# duaghter.net
KiCad netlist of a schematic drawn in EAGLE
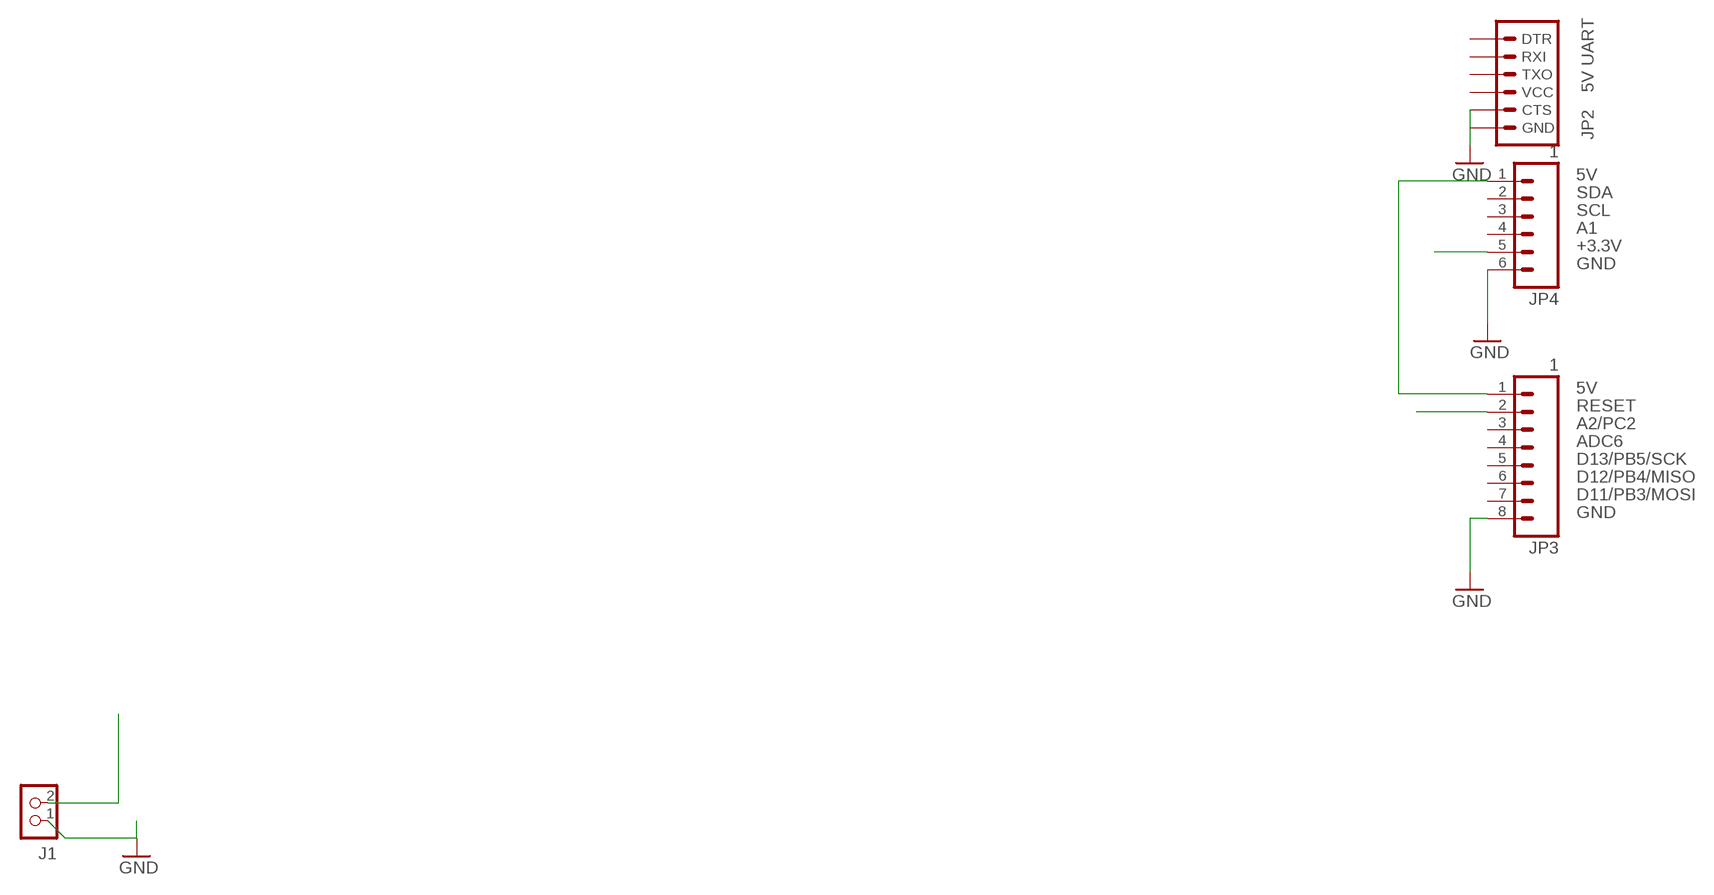
[diagram p0: schematic, sheet 1]

(export (version "E")
  (design (tool "Eeschema 10.0.6"))
  (components
    (comp (ref "J1")
      (value "12V input")
      (footprint "eagle-import:M1X2")
      (libsource (lib "eagle-import") (part "CON_HEADER_1X02-PTH"))
    )
    (comp (ref "JP2")
      (value "5V UART")
      (footprint "eagle-import:1X06")
      (libsource (lib "eagle-import") (part "ARDUINO_SERIAL_PROGRAMPTH"))
    )
    (comp (ref "JP3")
      (value "1")
      (footprint "eagle-import:1X08")
      (libsource (lib "eagle-import") (part "M081X08"))
    )
    (comp (ref "JP4")
      (value "1")
      (footprint "eagle-import:1X06")
      (libsource (lib "eagle-import") (part "M06SIP"))
    )
  )
  (nets
    (net (code "1") (name "/+3.3V") (class "Default")
      (node (ref "JP4") (pin "5") (pinfunction "5_5") (pintype "passive"))
    )
    (net (code "2") (name "/RESET") (class "Default")
      (node (ref "JP3") (pin "2") (pinfunction "2_2") (pintype "passive"))
    )
    (net (code "3") (name "GND") (class "Default")
      (node (ref "J1") (pin "1") (pinfunction "1_1") (pintype "passive"))
      (node (ref "JP2") (pin "5") (pinfunction "CTS_5") (pintype "passive"))
      (node (ref "JP2") (pin "6") (pinfunction "GND_6") (pintype "passive"))
      (node (ref "JP3") (pin "8") (pinfunction "8_8") (pintype "passive"))
      (node (ref "JP4") (pin "6") (pinfunction "6_6") (pintype "passive"))
    )
    (net (code "4") (name "Net-(JP3-Pad1)") (class "Default")
      (node (ref "JP3") (pin "1") (pinfunction "1_1") (pintype "passive"))
      (node (ref "JP4") (pin "1") (pinfunction "1_1") (pintype "passive"))
    )
    (net (code "5") (name "unconnected-(J1-Pad2)") (class "Default")
      (node (ref "J1") (pin "2") (pinfunction "2_2") (pintype "passive"))
    )
    (net (code "6") (name "unconnected-(JP2-DTR-Pad1)") (class "Default")
      (node (ref "JP2") (pin "1") (pinfunction "DTR_1") (pintype "passive"))
    )
    (net (code "7") (name "unconnected-(JP2-RXI-Pad2)") (class "Default")
      (node (ref "JP2") (pin "2") (pinfunction "RXI_2") (pintype "passive"))
    )
    (net (code "8") (name "unconnected-(JP2-TXO-Pad3)") (class "Default")
      (node (ref "JP2") (pin "3") (pinfunction "TXO_3") (pintype "passive"))
    )
    (net (code "9") (name "unconnected-(JP2-VCC-Pad4)") (class "Default")
      (node (ref "JP2") (pin "4") (pinfunction "VCC_4") (pintype "passive"))
    )
    (net (code "10") (name "unconnected-(JP3-Pad3)") (class "Default")
      (node (ref "JP3") (pin "3") (pinfunction "3_3") (pintype "passive"))
    )
    (net (code "11") (name "unconnected-(JP3-Pad4)") (class "Default")
      (node (ref "JP3") (pin "4") (pinfunction "4_4") (pintype "passive"))
    )
    (net (code "12") (name "unconnected-(JP3-Pad5)") (class "Default")
      (node (ref "JP3") (pin "5") (pinfunction "5_5") (pintype "passive"))
    )
    (net (code "13") (name "unconnected-(JP3-Pad6)") (class "Default")
      (node (ref "JP3") (pin "6") (pinfunction "6_6") (pintype "passive"))
    )
    (net (code "14") (name "unconnected-(JP3-Pad7)") (class "Default")
      (node (ref "JP3") (pin "7") (pinfunction "7_7") (pintype "passive"))
    )
    (net (code "15") (name "unconnected-(JP4-Pad2)") (class "Default")
      (node (ref "JP4") (pin "2") (pinfunction "2_2") (pintype "passive"))
    )
    (net (code "16") (name "unconnected-(JP4-Pad3)") (class "Default")
      (node (ref "JP4") (pin "3") (pinfunction "3_3") (pintype "passive"))
    )
    (net (code "17") (name "unconnected-(JP4-Pad4)") (class "Default")
      (node (ref "JP4") (pin "4") (pinfunction "4_4") (pintype "passive"))
    )
  )
)
